# hermesONE_v2_0.net
KiCad netlist of a schematic drawn in EAGLE
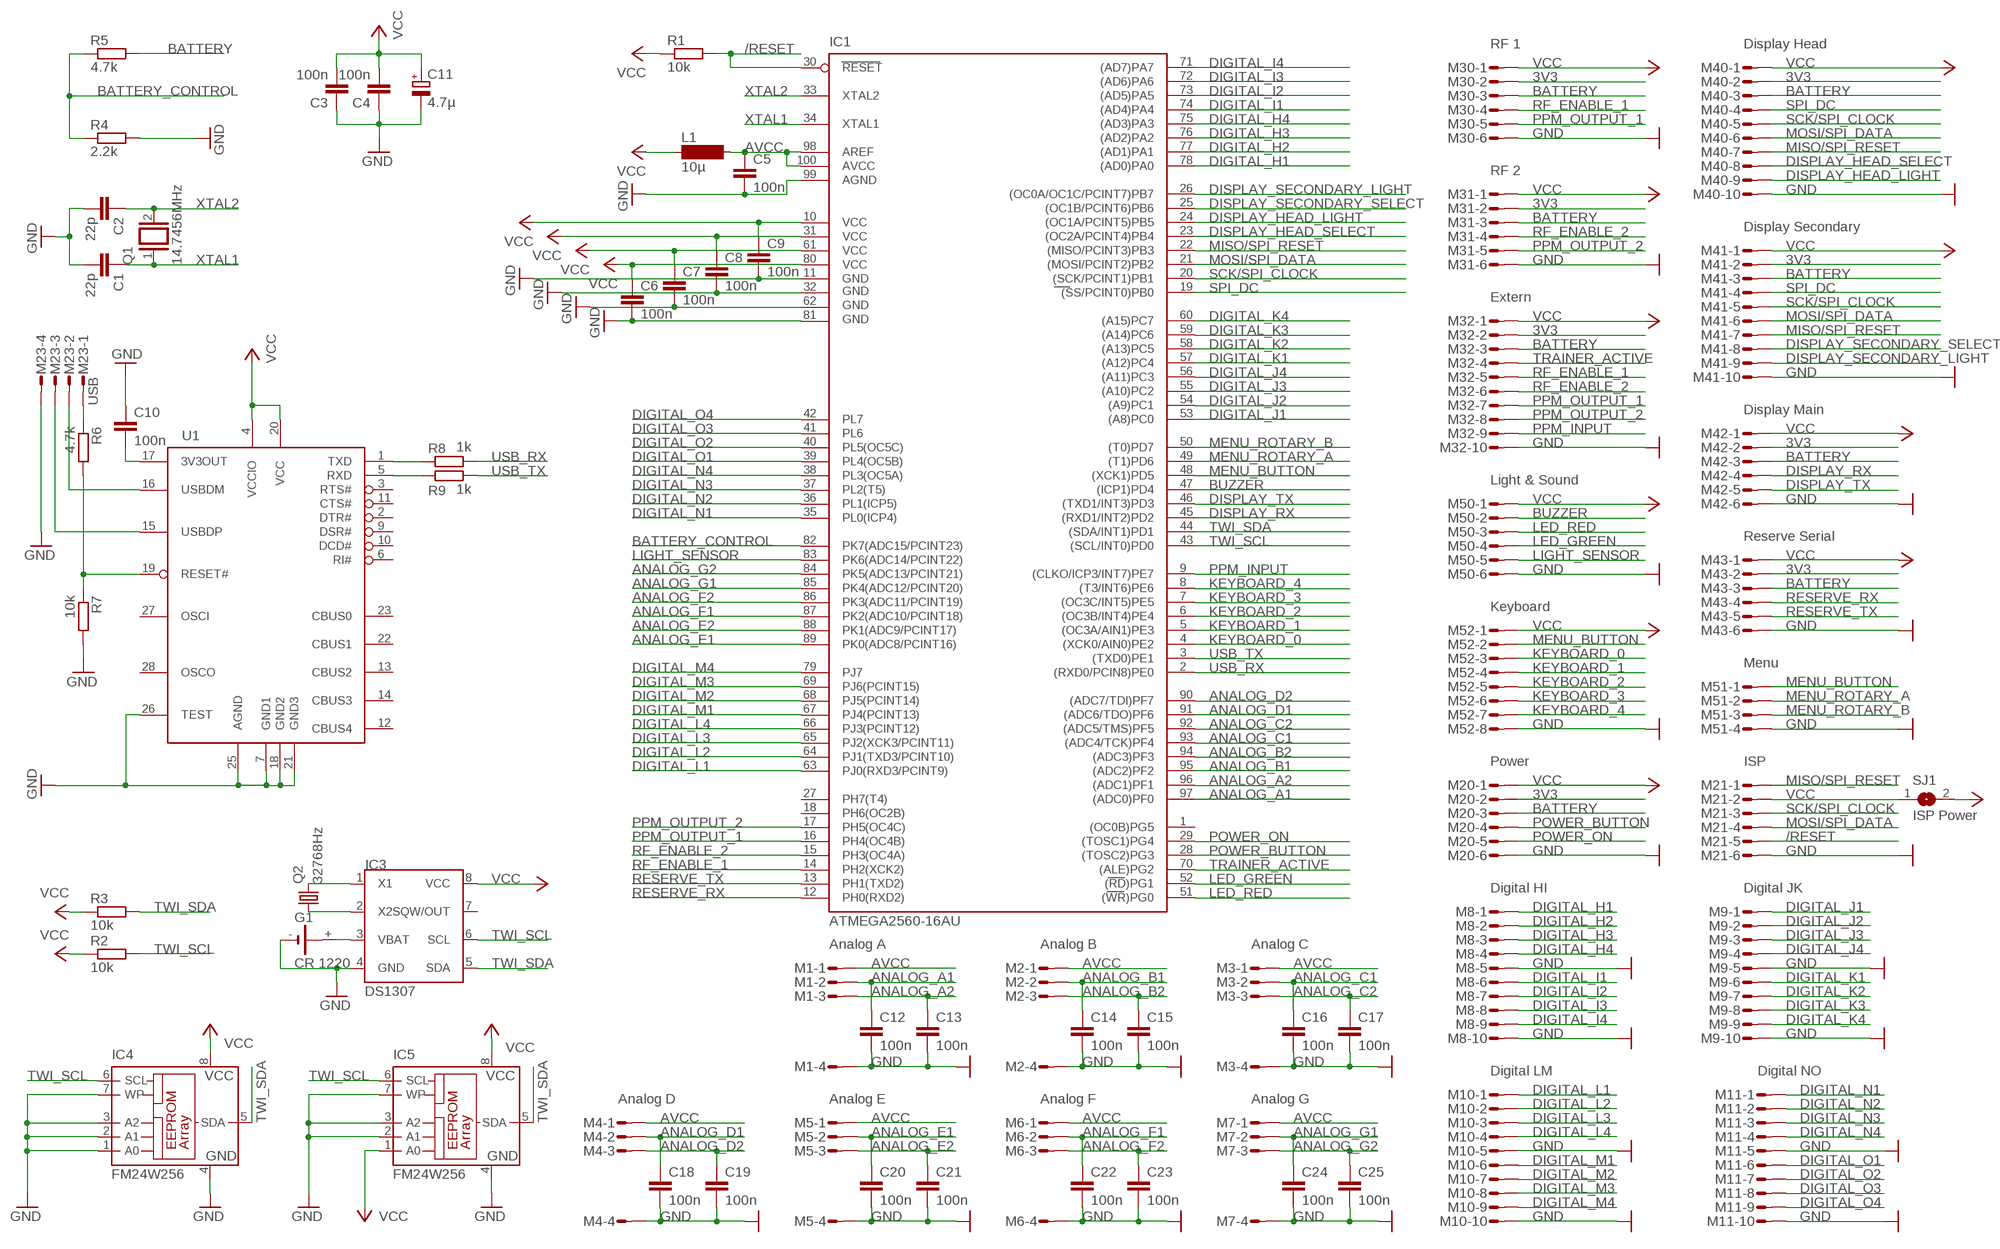
[diagram p0: schematic, sheet 1]

(export (version "E")
  (design (tool "Eeschema 10.0.6"))
  (components
    (comp (ref "C1")
      (value "22p")
      (footprint "eagle-import:C0603")
      (libsource (lib "eagle-import") (part "C-EUC0603"))
    )
    (comp (ref "C2")
      (value "22p")
      (footprint "eagle-import:C0603")
      (libsource (lib "eagle-import") (part "C-EUC0603"))
    )
    (comp (ref "C3")
      (value "100n")
      (footprint "eagle-import:C0603")
      (libsource (lib "eagle-import") (part "C-EUC0603"))
    )
    (comp (ref "C4")
      (value "100n")
      (footprint "eagle-import:C0603")
      (libsource (lib "eagle-import") (part "C-EUC0603"))
    )
    (comp (ref "C5")
      (value "100n")
      (footprint "eagle-import:C0603")
      (libsource (lib "eagle-import") (part "C-EUC0603"))
    )
    (comp (ref "C6")
      (value "100n")
      (footprint "eagle-import:C0603")
      (libsource (lib "eagle-import") (part "C-EUC0603"))
    )
    (comp (ref "C7")
      (value "100n")
      (footprint "eagle-import:C0603")
      (libsource (lib "eagle-import") (part "C-EUC0603"))
    )
    (comp (ref "C8")
      (value "100n")
      (footprint "eagle-import:C0603")
      (libsource (lib "eagle-import") (part "C-EUC0603"))
    )
    (comp (ref "C9")
      (value "100n")
      (footprint "eagle-import:C0603")
      (libsource (lib "eagle-import") (part "C-EUC0603"))
    )
    (comp (ref "C10")
      (value "100n")
      (footprint "eagle-import:C0603")
      (libsource (lib "eagle-import") (part "C-EUC0603"))
    )
    (comp (ref "C11")
      (value "4.7µ")
      (footprint "eagle-import:PANASONIC_B")
      (libsource (lib "eagle-import") (part "CPOL-EUB"))
    )
    (comp (ref "C12")
      (value "100n")
      (footprint "eagle-import:C0603")
      (libsource (lib "eagle-import") (part "C-EUC0603"))
    )
    (comp (ref "C13")
      (value "100n")
      (footprint "eagle-import:C0603")
      (libsource (lib "eagle-import") (part "C-EUC0603"))
    )
    (comp (ref "C14")
      (value "100n")
      (footprint "eagle-import:C0603")
      (libsource (lib "eagle-import") (part "C-EUC0603"))
    )
    (comp (ref "C15")
      (value "100n")
      (footprint "eagle-import:C0603")
      (libsource (lib "eagle-import") (part "C-EUC0603"))
    )
    (comp (ref "C16")
      (value "100n")
      (footprint "eagle-import:C0603")
      (libsource (lib "eagle-import") (part "C-EUC0603"))
    )
    (comp (ref "C17")
      (value "100n")
      (footprint "eagle-import:C0603")
      (libsource (lib "eagle-import") (part "C-EUC0603"))
    )
    (comp (ref "C18")
      (value "100n")
      (footprint "eagle-import:C0603")
      (libsource (lib "eagle-import") (part "C-EUC0603"))
    )
    (comp (ref "C19")
      (value "100n")
      (footprint "eagle-import:C0603")
      (libsource (lib "eagle-import") (part "C-EUC0603"))
    )
    (comp (ref "C20")
      (value "100n")
      (footprint "eagle-import:C0603")
      (libsource (lib "eagle-import") (part "C-EUC0603"))
    )
    (comp (ref "C21")
      (value "100n")
      (footprint "eagle-import:C0603")
      (libsource (lib "eagle-import") (part "C-EUC0603"))
    )
    (comp (ref "C22")
      (value "100n")
      (footprint "eagle-import:C0603")
      (libsource (lib "eagle-import") (part "C-EUC0603"))
    )
    (comp (ref "C23")
      (value "100n")
      (footprint "eagle-import:C0603")
      (libsource (lib "eagle-import") (part "C-EUC0603"))
    )
    (comp (ref "C24")
      (value "100n")
      (footprint "eagle-import:C0603")
      (libsource (lib "eagle-import") (part "C-EUC0603"))
    )
    (comp (ref "C25")
      (value "100n")
      (footprint "eagle-import:C0603")
      (libsource (lib "eagle-import") (part "C-EUC0603"))
    )
    (comp (ref "G1")
      (value "CR 1220")
      (footprint "eagle-import:KZH12THM")
      (libsource (lib "eagle-import") (part "1220"))
    )
    (comp (ref "IC1")
      (value "ATMEGA2560-16AU")
      (footprint "eagle-import:TQFP100")
      (libsource (lib "eagle-import") (part "ATMEGAAU2560-16"))
    )
    (comp (ref "IC3")
      (value "DS1307")
      (footprint "eagle-import:SOIC-8")
      (libsource (lib "eagle-import") (part "DS1307"))
    )
    (comp (ref "IC4")
      (value "FM24W256")
      (footprint "eagle-import:SO-08M")
      (fields (field (name "MF") "RAMTRON INTERNATIONAL CORP") (field (name "MPN") "FM24C64-S"))
      (libsource (lib "eagle-import") (part "24SMC64"))
    )
    (comp (ref "IC5")
      (value "FM24W256")
      (footprint "eagle-import:SO-08M")
      (fields (field (name "MF") "RAMTRON INTERNATIONAL CORP") (field (name "MPN") "FM24C64-S"))
      (libsource (lib "eagle-import") (part "24SMC64"))
    )
    (comp (ref "L1")
      (value "10µ")
      (footprint "eagle-import:SM-1206")
      (libsource (lib "eagle-import") (part "SM-1206"))
    )
    (comp (ref "M1")
      (value "Analog A")
      (footprint "eagle-import:MT-4")
      (fields (field (name "MPN") "7-215079-4"))
      (libsource (lib "eagle-import") (part "MT-4"))
    )
    (comp (ref "M2")
      (value "Analog B")
      (footprint "eagle-import:MT-4")
      (fields (field (name "MPN") "7-215079-4"))
      (libsource (lib "eagle-import") (part "MT-4"))
    )
    (comp (ref "M3")
      (value "Analog C")
      (footprint "eagle-import:MT-4")
      (fields (field (name "MPN") "7-215079-4"))
      (libsource (lib "eagle-import") (part "MT-4"))
    )
    (comp (ref "M4")
      (value "Analog D")
      (footprint "eagle-import:MT-4")
      (fields (field (name "MPN") "7-215079-4"))
      (libsource (lib "eagle-import") (part "MT-4"))
    )
    (comp (ref "M5")
      (value "Analog E")
      (footprint "eagle-import:MT-4")
      (fields (field (name "MPN") "7-215079-4"))
      (libsource (lib "eagle-import") (part "MT-4"))
    )
    (comp (ref "M6")
      (value "Analog F")
      (footprint "eagle-import:MT-4")
      (fields (field (name "MPN") "7-215079-4"))
      (libsource (lib "eagle-import") (part "MT-4"))
    )
    (comp (ref "M7")
      (value "Analog G")
      (footprint "eagle-import:MT-4")
      (fields (field (name "MPN") "7-215079-4"))
      (libsource (lib "eagle-import") (part "MT-4"))
    )
    (comp (ref "M8")
      (value "Digital HI")
      (footprint "eagle-import:MT-10")
      (fields (field (name "MF") "FARNELL") (field (name "MPN") "8-215079-0"))
      (libsource (lib "eagle-import") (part "MT-10"))
    )
    (comp (ref "M9")
      (value "Digital JK")
      (footprint "eagle-import:MT-10")
      (fields (field (name "MF") "FARNELL") (field (name "MPN") "8-215079-0"))
      (libsource (lib "eagle-import") (part "MT-10"))
    )
    (comp (ref "M10")
      (value "Digital LM")
      (footprint "eagle-import:MT-10")
      (fields (field (name "MF") "FARNELL") (field (name "MPN") "8-215079-0"))
      (libsource (lib "eagle-import") (part "MT-10"))
    )
    (comp (ref "M11")
      (value "Digital NO")
      (footprint "eagle-import:MT-10")
      (fields (field (name "MF") "FARNELL") (field (name "MPN") "8-215079-0"))
      (libsource (lib "eagle-import") (part "MT-10"))
    )
    (comp (ref "M20")
      (value "Power")
      (footprint "eagle-import:MT-6")
      (fields (field (name "MPN") "7-215079-6"))
      (libsource (lib "eagle-import") (part "MT-6"))
    )
    (comp (ref "M21")
      (value "ISP")
      (footprint "eagle-import:MT-6")
      (fields (field (name "MPN") "7-215079-6"))
      (libsource (lib "eagle-import") (part "MT-6"))
    )
    (comp (ref "M23")
      (value "USB")
      (footprint "eagle-import:MT-4")
      (fields (field (name "MPN") "7-215079-4"))
      (libsource (lib "eagle-import") (part "MT-4"))
    )
    (comp (ref "M30")
      (value "RF 1")
      (footprint "eagle-import:MT-6")
      (fields (field (name "MPN") "7-215079-6"))
      (libsource (lib "eagle-import") (part "MT-6"))
    )
    (comp (ref "M31")
      (value "RF 2")
      (footprint "eagle-import:MT-6")
      (fields (field (name "MPN") "7-215079-6"))
      (libsource (lib "eagle-import") (part "MT-6"))
    )
    (comp (ref "M32")
      (value "Extern")
      (footprint "eagle-import:MT-10")
      (fields (field (name "MF") "FARNELL") (field (name "MPN") "8-215079-0"))
      (libsource (lib "eagle-import") (part "MT-10"))
    )
    (comp (ref "M40")
      (value "Display Head")
      (footprint "eagle-import:MT-10")
      (fields (field (name "MF") "FARNELL") (field (name "MPN") "8-215079-0"))
      (libsource (lib "eagle-import") (part "MT-10"))
    )
    (comp (ref "M41")
      (value "Display Secondary")
      (footprint "eagle-import:MT-10")
      (fields (field (name "MF") "FARNELL") (field (name "MPN") "8-215079-0"))
      (libsource (lib "eagle-import") (part "MT-10"))
    )
    (comp (ref "M42")
      (value "Display Main")
      (footprint "eagle-import:MT-6")
      (fields (field (name "MPN") "7-215079-6"))
      (libsource (lib "eagle-import") (part "MT-6"))
    )
    (comp (ref "M43")
      (value "Reserve Serial")
      (footprint "eagle-import:MT-6")
      (fields (field (name "MPN") "7-215079-6"))
      (libsource (lib "eagle-import") (part "MT-6"))
    )
    (comp (ref "M50")
      (value "Light & Sound")
      (footprint "eagle-import:MT-6")
      (fields (field (name "MPN") "7-215079-6"))
      (libsource (lib "eagle-import") (part "MT-6"))
    )
    (comp (ref "M51")
      (value "Menu")
      (footprint "eagle-import:MT-4")
      (fields (field (name "MPN") "7-215079-4"))
      (libsource (lib "eagle-import") (part "MT-4"))
    )
    (comp (ref "M52")
      (value "Keyboard")
      (footprint "eagle-import:MT-8")
      (fields (field (name "MF") "FARNELL") (field (name "MPN") "7-215079-8"))
      (libsource (lib "eagle-import") (part "MT-8"))
    )
    (comp (ref "Q1")
      (value "14.7456MHz")
      (footprint "eagle-import:QS")
      (libsource (lib "eagle-import") (part "XTAL/S"))
    )
    (comp (ref "Q2")
      (value "32768Hz")
      (footprint "eagle-import:TC26H")
      (libsource (lib "eagle-import") (part "CRYSTALTC26H"))
    )
    (comp (ref "R1")
      (value "10k")
      (footprint "eagle-import:R0603")
      (libsource (lib "eagle-import") (part "R-EU_R0603"))
    )
    (comp (ref "R2")
      (value "10k")
      (footprint "eagle-import:R0603")
      (libsource (lib "eagle-import") (part "R-EU_R0603"))
    )
    (comp (ref "R3")
      (value "10k")
      (footprint "eagle-import:R0603")
      (libsource (lib "eagle-import") (part "R-EU_R0603"))
    )
    (comp (ref "R4")
      (value "2.2k")
      (footprint "eagle-import:R0603")
      (libsource (lib "eagle-import") (part "R-EU_R0603"))
    )
    (comp (ref "R5")
      (value "4.7k")
      (footprint "eagle-import:R0603")
      (libsource (lib "eagle-import") (part "R-EU_R0603"))
    )
    (comp (ref "R6")
      (value "4.7k")
      (footprint "eagle-import:R0603")
      (libsource (lib "eagle-import") (part "R-EU_R0603"))
    )
    (comp (ref "R7")
      (value "10k")
      (footprint "eagle-import:R0603")
      (libsource (lib "eagle-import") (part "R-EU_R0603"))
    )
    (comp (ref "R8")
      (value "1k")
      (footprint "eagle-import:R0603")
      (libsource (lib "eagle-import") (part "R-EU_R0603"))
    )
    (comp (ref "R9")
      (value "1k")
      (footprint "eagle-import:R0603")
      (libsource (lib "eagle-import") (part "R-EU_R0603"))
    )
    (comp (ref "SJ1")
      (value "ISP Power")
      (footprint "eagle-import:SJ")
      (libsource (lib "eagle-import") (part "SJ"))
    )
    (comp (ref "U1")
      (value "FT232R")
      (footprint "eagle-import:SSOP28DB")
      (libsource (lib "eagle-import") (part "FT232RL"))
    )
  )
  (nets
    (net (code "1") (name "/3V3") (class "Default")
      (node (ref "M20") (pin "2") (pinfunction "S_2") (pintype "passive"))
      (node (ref "M30") (pin "2") (pinfunction "S_2") (pintype "passive"))
      (node (ref "M31") (pin "2") (pinfunction "S_2") (pintype "passive"))
      (node (ref "M32") (pin "2") (pinfunction "S_2") (pintype "passive"))
      (node (ref "M40") (pin "2") (pinfunction "S_2") (pintype "passive"))
      (node (ref "M41") (pin "2") (pinfunction "S_2") (pintype "passive"))
      (node (ref "M42") (pin "2") (pinfunction "S_2") (pintype "passive"))
      (node (ref "M43") (pin "2") (pinfunction "S_2") (pintype "passive"))
    )
    (net (code "2") (name "/ANALOG_A1") (class "Default")
      (node (ref "C12") (pin "1") (pinfunction "1_1") (pintype "passive"))
      (node (ref "IC1") (pin "97") (pinfunction "(ADC0)PF0_97") (pintype "bidirectional"))
      (node (ref "M1") (pin "2") (pinfunction "S_2") (pintype "passive"))
    )
    (net (code "3") (name "/ANALOG_A2") (class "Default")
      (node (ref "C13") (pin "1") (pinfunction "1_1") (pintype "passive"))
      (node (ref "IC1") (pin "96") (pinfunction "(ADC1)PF1_96") (pintype "bidirectional"))
      (node (ref "M1") (pin "3") (pinfunction "S_3") (pintype "passive"))
    )
    (net (code "4") (name "/ANALOG_B1") (class "Default")
      (node (ref "C14") (pin "1") (pinfunction "1_1") (pintype "passive"))
      (node (ref "IC1") (pin "95") (pinfunction "(ADC2)PF2_95") (pintype "bidirectional"))
      (node (ref "M2") (pin "2") (pinfunction "S_2") (pintype "passive"))
    )
    (net (code "5") (name "/ANALOG_B2") (class "Default")
      (node (ref "C15") (pin "1") (pinfunction "1_1") (pintype "passive"))
      (node (ref "IC1") (pin "94") (pinfunction "(ADC3)PF3_94") (pintype "bidirectional"))
      (node (ref "M2") (pin "3") (pinfunction "S_3") (pintype "passive"))
    )
    (net (code "6") (name "/ANALOG_C1") (class "Default")
      (node (ref "C16") (pin "1") (pinfunction "1_1") (pintype "passive"))
      (node (ref "IC1") (pin "93") (pinfunction "(ADC4/TCK)PF4_93") (pintype "bidirectional"))
      (node (ref "M3") (pin "2") (pinfunction "S_2") (pintype "passive"))
    )
    (net (code "7") (name "/ANALOG_C2") (class "Default")
      (node (ref "C17") (pin "1") (pinfunction "1_1") (pintype "passive"))
      (node (ref "IC1") (pin "92") (pinfunction "(ADC5/TMS)PF5_92") (pintype "bidirectional"))
      (node (ref "M3") (pin "3") (pinfunction "S_3") (pintype "passive"))
    )
    (net (code "8") (name "/ANALOG_D1") (class "Default")
      (node (ref "C18") (pin "1") (pinfunction "1_1") (pintype "passive"))
      (node (ref "IC1") (pin "91") (pinfunction "(ADC6/TDO)PF6_91") (pintype "bidirectional"))
      (node (ref "M4") (pin "2") (pinfunction "S_2") (pintype "passive"))
    )
    (net (code "9") (name "/ANALOG_D2") (class "Default")
      (node (ref "C19") (pin "1") (pinfunction "1_1") (pintype "passive"))
      (node (ref "IC1") (pin "90") (pinfunction "(ADC7/TDI)PF7_90") (pintype "bidirectional"))
      (node (ref "M4") (pin "3") (pinfunction "S_3") (pintype "passive"))
    )
    (net (code "10") (name "/ANALOG_E1") (class "Default")
      (node (ref "C20") (pin "1") (pinfunction "1_1") (pintype "passive"))
      (node (ref "IC1") (pin "89") (pinfunction "PK0(ADC8/PCINT16)_89") (pintype "bidirectional"))
      (node (ref "M5") (pin "2") (pinfunction "S_2") (pintype "passive"))
    )
    (net (code "11") (name "/ANALOG_E2") (class "Default")
      (node (ref "C21") (pin "1") (pinfunction "1_1") (pintype "passive"))
      (node (ref "IC1") (pin "88") (pinfunction "PK1(ADC9/PCINT17)_88") (pintype "bidirectional"))
      (node (ref "M5") (pin "3") (pinfunction "S_3") (pintype "passive"))
    )
    (net (code "12") (name "/ANALOG_F1") (class "Default")
      (node (ref "C22") (pin "1") (pinfunction "1_1") (pintype "passive"))
      (node (ref "IC1") (pin "87") (pinfunction "PK2(ADC10/PCINT18)_87") (pintype "bidirectional"))
      (node (ref "M6") (pin "2") (pinfunction "S_2") (pintype "passive"))
    )
    (net (code "13") (name "/ANALOG_F2") (class "Default")
      (node (ref "C23") (pin "1") (pinfunction "1_1") (pintype "passive"))
      (node (ref "IC1") (pin "86") (pinfunction "PK3(ADC11/PCINT19)_86") (pintype "bidirectional"))
      (node (ref "M6") (pin "3") (pinfunction "S_3") (pintype "passive"))
    )
    (net (code "14") (name "/ANALOG_G1") (class "Default")
      (node (ref "C24") (pin "1") (pinfunction "1_1") (pintype "passive"))
      (node (ref "IC1") (pin "85") (pinfunction "PK4(ADC12/PCINT20)_85") (pintype "bidirectional"))
      (node (ref "M7") (pin "2") (pinfunction "S_2") (pintype "passive"))
    )
    (net (code "15") (name "/ANALOG_G2") (class "Default")
      (node (ref "C25") (pin "1") (pinfunction "1_1") (pintype "passive"))
      (node (ref "IC1") (pin "84") (pinfunction "PK5(ADC13/PCINT21)_84") (pintype "bidirectional"))
      (node (ref "M7") (pin "3") (pinfunction "S_3") (pintype "passive"))
    )
    (net (code "16") (name "/AVCC") (class "Default")
      (node (ref "C5") (pin "1") (pinfunction "1_1") (pintype "passive"))
      (node (ref "IC1") (pin "100") (pinfunction "AVCC_100") (pintype "power_in"))
      (node (ref "IC1") (pin "98") (pinfunction "AREF_98") (pintype "bidirectional"))
      (node (ref "L1") (pin "2") (pinfunction "2_2") (pintype "passive"))
      (node (ref "M1") (pin "1") (pinfunction "S_1") (pintype "passive"))
      (node (ref "M2") (pin "1") (pinfunction "S_1") (pintype "passive"))
      (node (ref "M3") (pin "1") (pinfunction "S_1") (pintype "passive"))
      (node (ref "M4") (pin "1") (pinfunction "S_1") (pintype "passive"))
      (node (ref "M5") (pin "1") (pinfunction "S_1") (pintype "passive"))
      (node (ref "M6") (pin "1") (pinfunction "S_1") (pintype "passive"))
      (node (ref "M7") (pin "1") (pinfunction "S_1") (pintype "passive"))
    )
    (net (code "17") (name "/BATTERY") (class "Default")
      (node (ref "M20") (pin "3") (pinfunction "S_3") (pintype "passive"))
      (node (ref "M30") (pin "3") (pinfunction "S_3") (pintype "passive"))
      (node (ref "M31") (pin "3") (pinfunction "S_3") (pintype "passive"))
      (node (ref "M32") (pin "3") (pinfunction "S_3") (pintype "passive"))
      (node (ref "M40") (pin "3") (pinfunction "S_3") (pintype "passive"))
      (node (ref "M41") (pin "3") (pinfunction "S_3") (pintype "passive"))
      (node (ref "M42") (pin "3") (pinfunction "S_3") (pintype "passive"))
      (node (ref "M43") (pin "3") (pinfunction "S_3") (pintype "passive"))
      (node (ref "R5") (pin "2") (pinfunction "2_2") (pintype "passive"))
    )
    (net (code "18") (name "/BATTERY_CONTROL") (class "Default")
      (node (ref "IC1") (pin "82") (pinfunction "PK7(ADC15/PCINT23)_82") (pintype "bidirectional"))
      (node (ref "R4") (pin "1") (pinfunction "1_1") (pintype "passive"))
      (node (ref "R5") (pin "1") (pinfunction "1_1") (pintype "passive"))
    )
    (net (code "19") (name "/BUZZER") (class "Default")
      (node (ref "IC1") (pin "47") (pinfunction "(ICP1)PD4_47") (pintype "bidirectional"))
      (node (ref "M50") (pin "2") (pinfunction "S_2") (pintype "passive"))
    )
    (net (code "20") (name "/DIGITAL_H1") (class "Default")
      (node (ref "IC1") (pin "78") (pinfunction "(AD0)PA0_78") (pintype "bidirectional"))
      (node (ref "M8") (pin "1") (pinfunction "S_1") (pintype "passive"))
    )
    (net (code "21") (name "/DIGITAL_H2") (class "Default")
      (node (ref "IC1") (pin "77") (pinfunction "(AD1)PA1_77") (pintype "bidirectional"))
      (node (ref "M8") (pin "2") (pinfunction "S_2") (pintype "passive"))
    )
    (net (code "22") (name "/DIGITAL_H3") (class "Default")
      (node (ref "IC1") (pin "76") (pinfunction "(AD2)PA2_76") (pintype "bidirectional"))
      (node (ref "M8") (pin "3") (pinfunction "S_3") (pintype "passive"))
    )
    (net (code "23") (name "/DIGITAL_H4") (class "Default")
      (node (ref "IC1") (pin "75") (pinfunction "(AD3)PA3_75") (pintype "bidirectional"))
      (node (ref "M8") (pin "4") (pinfunction "S_4") (pintype "passive"))
    )
    (net (code "24") (name "/DIGITAL_I1") (class "Default")
      (node (ref "IC1") (pin "74") (pinfunction "(AD4)PA4_74") (pintype "bidirectional"))
      (node (ref "M8") (pin "6") (pinfunction "S_6") (pintype "passive"))
    )
    (net (code "25") (name "/DIGITAL_I2") (class "Default")
      (node (ref "IC1") (pin "73") (pinfunction "(AD5)PA5_73") (pintype "bidirectional"))
      (node (ref "M8") (pin "7") (pinfunction "S_7") (pintype "passive"))
    )
    (net (code "26") (name "/DIGITAL_I3") (class "Default")
      (node (ref "IC1") (pin "72") (pinfunction "(AD6)PA6_72") (pintype "bidirectional"))
      (node (ref "M8") (pin "8") (pinfunction "S_8") (pintype "passive"))
    )
    (net (code "27") (name "/DIGITAL_I4") (class "Default")
      (node (ref "IC1") (pin "71") (pinfunction "(AD7)PA7_71") (pintype "bidirectional"))
      (node (ref "M8") (pin "9") (pinfunction "S_9") (pintype "passive"))
    )
    (net (code "28") (name "/DIGITAL_J1") (class "Default")
      (node (ref "IC1") (pin "53") (pinfunction "(A8)PC0_53") (pintype "bidirectional"))
      (node (ref "M9") (pin "1") (pinfunction "S_1") (pintype "passive"))
    )
    (net (code "29") (name "/DIGITAL_J2") (class "Default")
      (node (ref "IC1") (pin "54") (pinfunction "(A9)PC1_54") (pintype "bidirectional"))
      (node (ref "M9") (pin "2") (pinfunction "S_2") (pintype "passive"))
    )
    (net (code "30") (name "/DIGITAL_J3") (class "Default")
      (node (ref "IC1") (pin "55") (pinfunction "(A10)PC2_55") (pintype "bidirectional"))
      (node (ref "M9") (pin "3") (pinfunction "S_3") (pintype "passive"))
    )
    (net (code "31") (name "/DIGITAL_J4") (class "Default")
      (node (ref "IC1") (pin "56") (pinfunction "(A11)PC3_56") (pintype "bidirectional"))
      (node (ref "M9") (pin "4") (pinfunction "S_4") (pintype "passive"))
    )
    (net (code "32") (name "/DIGITAL_K1") (class "Default")
      (node (ref "IC1") (pin "57") (pinfunction "(A12)PC4_57") (pintype "bidirectional"))
      (node (ref "M9") (pin "6") (pinfunction "S_6") (pintype "passive"))
    )
    (net (code "33") (name "/DIGITAL_K2") (class "Default")
      (node (ref "IC1") (pin "58") (pinfunction "(A13)PC5_58") (pintype "bidirectional"))
      (node (ref "M9") (pin "7") (pinfunction "S_7") (pintype "passive"))
    )
    (net (code "34") (name "/DIGITAL_K3") (class "Default")
      (node (ref "IC1") (pin "59") (pinfunction "(A14)PC6_59") (pintype "bidirectional"))
      (node (ref "M9") (pin "8") (pinfunction "S_8") (pintype "passive"))
    )
    (net (code "35") (name "/DIGITAL_K4") (class "Default")
      (node (ref "IC1") (pin "60") (pinfunction "(A15)PC7_60") (pintype "bidirectional"))
      (node (ref "M9") (pin "9") (pinfunction "S_9") (pintype "passive"))
    )
    (net (code "36") (name "/DIGITAL_L1") (class "Default")
      (node (ref "IC1") (pin "63") (pinfunction "PJ0(RXD3/PCINT9)_63") (pintype "bidirectional"))
      (node (ref "M10") (pin "1") (pinfunction "S_1") (pintype "passive"))
    )
    (net (code "37") (name "/DIGITAL_L2") (class "Default")
      (node (ref "IC1") (pin "64") (pinfunction "PJ1(TXD3/PCINT10)_64") (pintype "bidirectional"))
      (node (ref "M10") (pin "2") (pinfunction "S_2") (pintype "passive"))
    )
    (net (code "38") (name "/DIGITAL_L3") (class "Default")
      (node (ref "IC1") (pin "65") (pinfunction "PJ2(XCK3/PCINT11)_65") (pintype "bidirectional"))
      (node (ref "M10") (pin "3") (pinfunction "S_3") (pintype "passive"))
    )
    (net (code "39") (name "/DIGITAL_L4") (class "Default")
      (node (ref "IC1") (pin "66") (pinfunction "PJ3(PCINT12)_66") (pintype "bidirectional"))
      (node (ref "M10") (pin "4") (pinfunction "S_4") (pintype "passive"))
    )
    (net (code "40") (name "/DIGITAL_M1") (class "Default")
      (node (ref "IC1") (pin "67") (pinfunction "PJ4(PCINT13)_67") (pintype "bidirectional"))
      (node (ref "M10") (pin "6") (pinfunction "S_6") (pintype "passive"))
    )
    (net (code "41") (name "/DIGITAL_M2") (class "Default")
      (node (ref "IC1") (pin "68") (pinfunction "PJ5(PCINT14)_68") (pintype "bidirectional"))
      (node (ref "M10") (pin "7") (pinfunction "S_7") (pintype "passive"))
    )
    (net (code "42") (name "/DIGITAL_M3") (class "Default")
      (node (ref "IC1") (pin "69") (pinfunction "PJ6(PCINT15)_69") (pintype "bidirectional"))
      (node (ref "M10") (pin "8") (pinfunction "S_8") (pintype "passive"))
    )
    (net (code "43") (name "/DIGITAL_M4") (class "Default")
      (node (ref "IC1") (pin "79") (pinfunction "PJ7_79") (pintype "bidirectional"))
      (node (ref "M10") (pin "9") (pinfunction "S_9") (pintype "passive"))
    )
    (net (code "44") (name "/DIGITAL_N1") (class "Default")
      (node (ref "IC1") (pin "35") (pinfunction "PL0(ICP4)_35") (pintype "bidirectional"))
      (node (ref "M11") (pin "1") (pinfunction "S_1") (pintype "passive"))
    )
    (net (code "45") (name "/DIGITAL_N2") (class "Default")
      (node (ref "IC1") (pin "36") (pinfunction "PL1(ICP5)_36") (pintype "bidirectional"))
      (node (ref "M11") (pin "2") (pinfunction "S_2") (pintype "passive"))
    )
    (net (code "46") (name "/DIGITAL_N3") (class "Default")
      (node (ref "IC1") (pin "37") (pinfunction "PL2(T5)_37") (pintype "bidirectional"))
      (node (ref "M11") (pin "3") (pinfunction "S_3") (pintype "passive"))
    )
    (net (code "47") (name "/DIGITAL_N4") (class "Default")
      (node (ref "IC1") (pin "38") (pinfunction "PL3(OC5A)_38") (pintype "bidirectional"))
      (node (ref "M11") (pin "4") (pinfunction "S_4") (pintype "passive"))
    )
    (net (code "48") (name "/DIGITAL_O1") (class "Default")
      (node (ref "IC1") (pin "39") (pinfunction "PL4(OC5B)_39") (pintype "bidirectional"))
      (node (ref "M11") (pin "6") (pinfunction "S_6") (pintype "passive"))
    )
    (net (code "49") (name "/DIGITAL_O2") (class "Default")
      (node (ref "IC1") (pin "40") (pinfunction "PL5(OC5C)_40") (pintype "bidirectional"))
      (node (ref "M11") (pin "7") (pinfunction "S_7") (pintype "passive"))
    )
    (net (code "50") (name "/DIGITAL_O3") (class "Default")
      (node (ref "IC1") (pin "41") (pinfunction "PL6_41") (pintype "bidirectional"))
      (node (ref "M11") (pin "8") (pinfunction "S_8") (pintype "passive"))
    )
    (net (code "51") (name "/DIGITAL_O4") (class "Default")
      (node (ref "IC1") (pin "42") (pinfunction "PL7_42") (pintype "bidirectional"))
      (node (ref "M11") (pin "9") (pinfunction "S_9") (pintype "passive"))
    )
    (net (code "52") (name "/DISPLAY_HEAD_LIGHT") (class "Default")
      (node (ref "IC1") (pin "24") (pinfunction "(OC1A/PCINT5)PB5_24") (pintype "bidirectional"))
      (node (ref "M40") (pin "9") (pinfunction "S_9") (pintype "passive"))
    )
    (net (code "53") (name "/DISPLAY_HEAD_SELECT") (class "Default")
      (node (ref "IC1") (pin "23") (pinfunction "(OC2A/PCINT4)PB4_23") (pintype "bidirectional"))
      (node (ref "M40") (pin "8") (pinfunction "S_8") (pintype "passive"))
    )
    (net (code "54") (name "/DISPLAY_RX") (class "Default")
      (node (ref "IC1") (pin "45") (pinfunction "(RXD1/INT2)PD2_45") (pintype "bidirectional"))
      (node (ref "M42") (pin "4") (pinfunction "S_4") (pintype "passive"))
    )
    (net (code "55") (name "/DISPLAY_SECONDARY_LIGHT") (class "Default")
      (node (ref "IC1") (pin "26") (pinfunction "(OC0A/OC1C/PCINT7)PB7_26") (pintype "bidirectional"))
      (node (ref "M41") (pin "9") (pinfunction "S_9") (pintype "passive"))
    )
    (net (code "56") (name "/DISPLAY_SECONDARY_SELECT") (class "Default")
      (node (ref "IC1") (pin "25") (pinfunction "(OC1B/PCINT6)PB6_25") (pintype "bidirectional"))
      (node (ref "M41") (pin "8") (pinfunction "S_8") (pintype "passive"))
    )
    (net (code "57") (name "/DISPLAY_TX") (class "Default")
      (node (ref "IC1") (pin "46") (pinfunction "(TXD1/INT3)PD3_46") (pintype "bidirectional"))
      (node (ref "M42") (pin "5") (pinfunction "S_5") (pintype "passive"))
    )
    (net (code "58") (name "/KEYBOARD_0") (class "Default")
      (node (ref "IC1") (pin "4") (pinfunction "(XCK0/AIN0)PE2_4") (pintype "bidirectional"))
      (node (ref "M52") (pin "3") (pinfunction "S_3") (pintype "passive"))
    )
    (net (code "59") (name "/KEYBOARD_1") (class "Default")
      (node (ref "IC1") (pin "5") (pinfunction "(OC3A/AIN1)PE3_5") (pintype "bidirectional"))
      (node (ref "M52") (pin "4") (pinfunction "S_4") (pintype "passive"))
    )
    (net (code "60") (name "/KEYBOARD_2") (class "Default")
      (node (ref "IC1") (pin "6") (pinfunction "(OC3B/INT4)PE4_6") (pintype "bidirectional"))
      (node (ref "M52") (pin "5") (pinfunction "S_5") (pintype "passive"))
    )
    (net (code "61") (name "/KEYBOARD_3") (class "Default")
      (node (ref "IC1") (pin "7") (pinfunction "(OC3C/INT5)PE5_7") (pintype "bidirectional"))
      (node (ref "M52") (pin "6") (pinfunction "S_6") (pintype "passive"))
    )
    (net (code "62") (name "/KEYBOARD_4") (class "Default")
      (node (ref "IC1") (pin "8") (pinfunction "(T3/INT6)PE6_8") (pintype "bidirectional"))
      (node (ref "M52") (pin "7") (pinfunction "S_7") (pintype "passive"))
    )
    (net (code "63") (name "/LED_GREEN") (class "Default")
      (node (ref "IC1") (pin "52") (pinfunction "(RD)PG1_52") (pintype "bidirectional"))
      (node (ref "M50") (pin "4") (pinfunction "S_4") (pintype "passive"))
    )
    (net (code "64") (name "/LED_RED") (class "Default")
      (node (ref "IC1") (pin "51") (pinfunction "(WR)PG0_51") (pintype "bidirectional"))
      (node (ref "M50") (pin "3") (pinfunction "S_3") (pintype "passive"))
    )
    (net (code "65") (name "/LIGHT_SENSOR") (class "Default")
      (node (ref "IC1") (pin "83") (pinfunction "PK6(ADC14/PCINT22)_83") (pintype "bidirectional"))
      (node (ref "M50") (pin "5") (pinfunction "S_5") (pintype "passive"))
    )
    (net (code "66") (name "/MENU_BUTTON") (class "Default")
      (node (ref "IC1") (pin "48") (pinfunction "(XCK1)PD5_48") (pintype "bidirectional"))
      (node (ref "M51") (pin "1") (pinfunction "S_1") (pintype "passive"))
      (node (ref "M52") (pin "2") (pinfunction "S_2") (pintype "passive"))
    )
    (net (code "67") (name "/MENU_ROTARY_A") (class "Default")
      (node (ref "IC1") (pin "49") (pinfunction "(T1)PD6_49") (pintype "bidirectional"))
      (node (ref "M51") (pin "2") (pinfunction "S_2") (pintype "passive"))
    )
    (net (code "68") (name "/MENU_ROTARY_B") (class "Default")
      (node (ref "IC1") (pin "50") (pinfunction "(T0)PD7_50") (pintype "bidirectional"))
      (node (ref "M51") (pin "3") (pinfunction "S_3") (pintype "passive"))
    )
    (net (code "69") (name "/MISO{slash}SPI_RESET") (class "Default")
      (node (ref "IC1") (pin "22") (pinfunction "(MISO/PCINT3)PB3_22") (pintype "bidirectional"))
      (node (ref "M21") (pin "1") (pinfunction "S_1") (pintype "passive"))
      (node (ref "M40") (pin "7") (pinfunction "S_7") (pintype "passive"))
      (node (ref "M41") (pin "7") (pinfunction "S_7") (pintype "passive"))
    )
    (net (code "70") (name "/MOSI{slash}SPI_DATA") (class "Default")
      (node (ref "IC1") (pin "21") (pinfunction "(MOSI/PCINT2)PB2_21") (pintype "bidirectional"))
      (node (ref "M21") (pin "4") (pinfunction "S_4") (pintype "passive"))
      (node (ref "M40") (pin "6") (pinfunction "S_6") (pintype "passive"))
      (node (ref "M41") (pin "6") (pinfunction "S_6") (pintype "passive"))
    )
    (net (code "71") (name "/POWER_BUTTON") (class "Default")
      (node (ref "IC1") (pin "28") (pinfunction "(TOSC2)PG3_28") (pintype "bidirectional"))
      (node (ref "M20") (pin "4") (pinfunction "S_4") (pintype "passive"))
    )
    (net (code "72") (name "/POWER_ON") (class "Default")
      (node (ref "IC1") (pin "29") (pinfunction "(TOSC1)PG4_29") (pintype "bidirectional"))
      (node (ref "M20") (pin "5") (pinfunction "S_5") (pintype "passive"))
    )
    (net (code "73") (name "/PPM_INPUT") (class "Default")
      (node (ref "IC1") (pin "9") (pinfunction "(CLKO/ICP3/INT7)PE7_9") (pintype "bidirectional"))
      (node (ref "M32") (pin "9") (pinfunction "S_9") (pintype "passive"))
    )
    (net (code "74") (name "/PPM_OUTPUT_1") (class "Default")
      (node (ref "IC1") (pin "16") (pinfunction "PH4(OC4B)_16") (pintype "bidirectional"))
      (node (ref "M30") (pin "5") (pinfunction "S_5") (pintype "passive"))
      (node (ref "M32") (pin "7") (pinfunction "S_7") (pintype "passive"))
    )
    (net (code "75") (name "/PPM_OUTPUT_2") (class "Default")
      (node (ref "IC1") (pin "17") (pinfunction "PH5(OC4C)_17") (pintype "bidirectional"))
      (node (ref "M31") (pin "5") (pinfunction "S_5") (pintype "passive"))
      (node (ref "M32") (pin "8") (pinfunction "S_8") (pintype "passive"))
    )
    (net (code "76") (name "/RESERVE_RX") (class "Default")
      (node (ref "IC1") (pin "12") (pinfunction "PH0(RXD2)_12") (pintype "bidirectional"))
      (node (ref "M43") (pin "4") (pinfunction "S_4") (pintype "passive"))
    )
    (net (code "77") (name "/RESERVE_TX") (class "Default")
      (node (ref "IC1") (pin "13") (pinfunction "PH1(TXD2)_13") (pintype "bidirectional"))
      (node (ref "M43") (pin "5") (pinfunction "S_5") (pintype "passive"))
    )
    (net (code "78") (name "/RF_ENABLE_1") (class "Default")
      (node (ref "IC1") (pin "14") (pinfunction "PH2(XCK2)_14") (pintype "bidirectional"))
      (node (ref "M30") (pin "4") (pinfunction "S_4") (pintype "passive"))
      (node (ref "M32") (pin "5") (pinfunction "S_5") (pintype "passive"))
    )
    (net (code "79") (name "/RF_ENABLE_2") (class "Default")
      (node (ref "IC1") (pin "15") (pinfunction "PH3(OC4A)_15") (pintype "bidirectional"))
      (node (ref "M31") (pin "4") (pinfunction "S_4") (pintype "passive"))
      (node (ref "M32") (pin "6") (pinfunction "S_6") (pintype "passive"))
    )
    (net (code "80") (name "/SCK{slash}SPI_CLOCK") (class "Default")
      (node (ref "IC1") (pin "20") (pinfunction "(SCK/PCINT1)PB1_20") (pintype "bidirectional"))
      (node (ref "M21") (pin "3") (pinfunction "S_3") (pintype "passive"))
      (node (ref "M40") (pin "5") (pinfunction "S_5") (pintype "passive"))
      (node (ref "M41") (pin "5") (pinfunction "S_5") (pintype "passive"))
    )
    (net (code "81") (name "/SPI_DC") (class "Default")
      (node (ref "IC1") (pin "19") (pinfunction "(SS/PCINT0)PB0_19") (pintype "bidirectional"))
      (node (ref "M40") (pin "4") (pinfunction "S_4") (pintype "passive"))
      (node (ref "M41") (pin "4") (pinfunction "S_4") (pintype "passive"))
    )
    (net (code "82") (name "/TRAINER_ACTIVE") (class "Default")
      (node (ref "IC1") (pin "70") (pinfunction "(ALE)PG2_70") (pintype "bidirectional"))
      (node (ref "M32") (pin "4") (pinfunction "S_4") (pintype "passive"))
    )
    (net (code "83") (name "/TWI_SCL") (class "Default")
      (node (ref "IC1") (pin "43") (pinfunction "(SCL/INT0)PD0_43") (pintype "bidirectional"))
      (node (ref "IC3") (pin "6") (pinfunction "SCL_6") (pintype "input"))
      (node (ref "IC4") (pin "6") (pinfunction "SCL_6") (pintype "input"))
      (node (ref "IC5") (pin "6") (pinfunction "SCL_6") (pintype "input"))
      (node (ref "R2") (pin "2") (pinfunction "2_2") (pintype "passive"))
    )
    (net (code "84") (name "/TWI_SDA") (class "Default")
      (node (ref "IC1") (pin "44") (pinfunction "(SDA/INT1)PD1_44") (pintype "bidirectional"))
      (node (ref "IC3") (pin "5") (pinfunction "SDA_5") (pintype "bidirectional"))
      (node (ref "IC4") (pin "5") (pinfunction "SDA_5") (pintype "bidirectional"))
      (node (ref "IC5") (pin "5") (pinfunction "SDA_5") (pintype "bidirectional"))
      (node (ref "R3") (pin "2") (pinfunction "2_2") (pintype "passive"))
    )
    (net (code "85") (name "/USB_RX") (class "Default")
      (node (ref "IC1") (pin "2") (pinfunction "(RXD0/PCIN8)PE0_2") (pintype "bidirectional"))
      (node (ref "R8") (pin "2") (pinfunction "2_2") (pintype "passive"))
    )
    (net (code "86") (name "/USB_TX") (class "Default")
      (node (ref "IC1") (pin "3") (pinfunction "(TXD0)PE1_3") (pintype "bidirectional"))
      (node (ref "R9") (pin "2") (pinfunction "2_2") (pintype "passive"))
    )
    (net (code "87") (name "/XTAL1") (class "Default")
      (node (ref "C1") (pin "1") (pinfunction "1_1") (pintype "passive"))
      (node (ref "IC1") (pin "34") (pinfunction "XTAL1_34") (pintype "input"))
      (node (ref "Q1") (pin "1") (pinfunction "1_1") (pintype "passive"))
    )
    (net (code "88") (name "/XTAL2") (class "Default")
      (node (ref "C2") (pin "1") (pinfunction "1_1") (pintype "passive"))
      (node (ref "IC1") (pin "33") (pinfunction "XTAL2_33") (pintype "output"))
      (node (ref "Q1") (pin "2") (pinfunction "2_2") (pintype "passive"))
    )
    (net (code "89") (name "/{slash}RESET") (class "Default")
      (node (ref "IC1") (pin "30") (pinfunction "RESET_30") (pintype "input"))
      (node (ref "M21") (pin "5") (pinfunction "S_5") (pintype "passive"))
      (node (ref "R1") (pin "2") (pinfunction "2_2") (pintype "passive"))
    )
    (net (code "90") (name "GND") (class "Default")
      (node (ref "C1") (pin "2") (pinfunction "2_2") (pintype "passive"))
      (node (ref "C10") (pin "1") (pinfunction "1_1") (pintype "passive"))
      (node (ref "C11") (pin "-") (pinfunction "-_-") (pintype "passive"))
      (node (ref "C12") (pin "2") (pinfunction "2_2") (pintype "passive"))
      (node (ref "C13") (pin "2") (pinfunction "2_2") (pintype "passive"))
      (node (ref "C14") (pin "2") (pinfunction "2_2") (pintype "passive"))
      (node (ref "C15") (pin "2") (pinfunction "2_2") (pintype "passive"))
      (node (ref "C16") (pin "2") (pinfunction "2_2") (pintype "passive"))
      (node (ref "C17") (pin "2") (pinfunction "2_2") (pintype "passive"))
      (node (ref "C18") (pin "2") (pinfunction "2_2") (pintype "passive"))
      (node (ref "C19") (pin "2") (pinfunction "2_2") (pintype "passive"))
      (node (ref "C2") (pin "2") (pinfunction "2_2") (pintype "passive"))
      (node (ref "C20") (pin "2") (pinfunction "2_2") (pintype "passive"))
      (node (ref "C21") (pin "2") (pinfunction "2_2") (pintype "passive"))
      (node (ref "C22") (pin "2") (pinfunction "2_2") (pintype "passive"))
      (node (ref "C23") (pin "2") (pinfunction "2_2") (pintype "passive"))
      (node (ref "C24") (pin "2") (pinfunction "2_2") (pintype "passive"))
      (node (ref "C25") (pin "2") (pinfunction "2_2") (pintype "passive"))
      (node (ref "C3") (pin "1") (pinfunction "1_1") (pintype "passive"))
      (node (ref "C4") (pin "1") (pinfunction "1_1") (pintype "passive"))
      (node (ref "C5") (pin "2") (pinfunction "2_2") (pintype "passive"))
      (node (ref "C6") (pin "2") (pinfunction "2_2") (pintype "passive"))
      (node (ref "C7") (pin "2") (pinfunction "2_2") (pintype "passive"))
      (node (ref "C8") (pin "2") (pinfunction "2_2") (pintype "passive"))
      (node (ref "C9") (pin "2") (pinfunction "2_2") (pintype "passive"))
      (node (ref "G1") (pin "-") (pinfunction "-_-") (pintype "passive"))
      (node (ref "IC1") (pin "11") (pinfunction "GND_11") (pintype "power_in"))
      (node (ref "IC1") (pin "32") (pinfunction "GND1_32") (pintype "power_in"))
      (node (ref "IC1") (pin "62") (pinfunction "GND2_62") (pintype "power_in"))
      (node (ref "IC1") (pin "81") (pinfunction "GND3_81") (pintype "power_in"))
      (node (ref "IC1") (pin "99") (pinfunction "AGND_99") (pintype "power_in"))
      (node (ref "IC3") (pin "4") (pinfunction "GND_4") (pintype "power_in"))
      (node (ref "IC4") (pin "1") (pinfunction "A0_1") (pintype "input"))
      (node (ref "IC4") (pin "2") (pinfunction "A1_2") (pintype "input"))
      (node (ref "IC4") (pin "3") (pinfunction "A2_3") (pintype "input"))
      (node (ref "IC4") (pin "4") (pinfunction "GND_4") (pintype "power_in"))
      (node (ref "IC4") (pin "7") (pinfunction "WP_7") (pintype "input"))
      (node (ref "IC5") (pin "2") (pinfunction "A1_2") (pintype "input"))
      (node (ref "IC5") (pin "3") (pinfunction "A2_3") (pintype "input"))
      (node (ref "IC5") (pin "4") (pinfunction "GND_4") (pintype "power_in"))
      (node (ref "IC5") (pin "7") (pinfunction "WP_7") (pintype "input"))
      (node (ref "M1") (pin "4") (pinfunction "S_4") (pintype "passive"))
      (node (ref "M10") (pin "10") (pinfunction "S_10") (pintype "passive"))
      (node (ref "M10") (pin "5") (pinfunction "S_5") (pintype "passive"))
      (node (ref "M11") (pin "10") (pinfunction "S_10") (pintype "passive"))
      (node (ref "M11") (pin "5") (pinfunction "S_5") (pintype "passive"))
      (node (ref "M2") (pin "4") (pinfunction "S_4") (pintype "passive"))
      (node (ref "M20") (pin "6") (pinfunction "S_6") (pintype "passive"))
      (node (ref "M21") (pin "6") (pinfunction "S_6") (pintype "passive"))
      (node (ref "M23") (pin "4") (pinfunction "S_4") (pintype "passive"))
      (node (ref "M3") (pin "4") (pinfunction "S_4") (pintype "passive"))
      (node (ref "M30") (pin "6") (pinfunction "S_6") (pintype "passive"))
      (node (ref "M31") (pin "6") (pinfunction "S_6") (pintype "passive"))
      (node (ref "M32") (pin "10") (pinfunction "S_10") (pintype "passive"))
      (node (ref "M4") (pin "4") (pinfunction "S_4") (pintype "passive"))
      (node (ref "M40") (pin "10") (pinfunction "S_10") (pintype "passive"))
      (node (ref "M41") (pin "10") (pinfunction "S_10") (pintype "passive"))
      (node (ref "M42") (pin "6") (pinfunction "S_6") (pintype "passive"))
      (node (ref "M43") (pin "6") (pinfunction "S_6") (pintype "passive"))
      (node (ref "M5") (pin "4") (pinfunction "S_4") (pintype "passive"))
      (node (ref "M50") (pin "6") (pinfunction "S_6") (pintype "passive"))
      (node (ref "M51") (pin "4") (pinfunction "S_4") (pintype "passive"))
      (node (ref "M52") (pin "8") (pinfunction "S_8") (pintype "passive"))
      (node (ref "M6") (pin "4") (pinfunction "S_4") (pintype "passive"))
      (node (ref "M7") (pin "4") (pinfunction "S_4") (pintype "passive"))
      (node (ref "M8") (pin "10") (pinfunction "S_10") (pintype "passive"))
      (node (ref "M8") (pin "5") (pinfunction "S_5") (pintype "passive"))
      (node (ref "M9") (pin "10") (pinfunction "S_10") (pintype "passive"))
      (node (ref "M9") (pin "5") (pinfunction "S_5") (pintype "passive"))
      (node (ref "R4") (pin "2") (pinfunction "2_2") (pintype "passive"))
      (node (ref "R7") (pin "2") (pinfunction "2_2") (pintype "passive"))
      (node (ref "U1") (pin "18") (pinfunction "GND2_18") (pintype "power_in"))
      (node (ref "U1") (pin "21") (pinfunction "GND3_21") (pintype "power_in"))
      (node (ref "U1") (pin "25") (pinfunction "AGND_25") (pintype "power_in"))
      (node (ref "U1") (pin "26") (pinfunction "TEST_26") (pintype "input"))
      (node (ref "U1") (pin "7") (pinfunction "GND1_7") (pintype "power_in"))
    )
    (net (code "91") (name "Net-(IC3-VBAT)") (class "Default")
      (node (ref "G1") (pin "+") (pinfunction "+_+") (pintype "passive"))
      (node (ref "IC3") (pin "3") (pinfunction "VBAT_3") (pintype "power_in"))
    )
    (net (code "92") (name "Net-(IC3-X1)") (class "Default")
      (node (ref "IC3") (pin "1") (pinfunction "X1_1") (pintype "input"))
      (node (ref "Q2") (pin "2") (pinfunction "2_2") (pintype "passive"))
    )
    (net (code "93") (name "Net-(IC3-X2)") (class "Default")
      (node (ref "IC3") (pin "2") (pinfunction "X2_2") (pintype "output"))
      (node (ref "Q2") (pin "1") (pinfunction "1_1") (pintype "passive"))
    )
    (net (code "94") (name "Net-(M21B-S)") (class "Default")
      (node (ref "M21") (pin "2") (pinfunction "S_2") (pintype "passive"))
      (node (ref "SJ1") (pin "1") (pinfunction "1_1") (pintype "passive"))
    )
    (net (code "95") (name "Net-(M23A-S)") (class "Default")
      (node (ref "M23") (pin "1") (pinfunction "S_1") (pintype "passive"))
      (node (ref "R6") (pin "1") (pinfunction "1_1") (pintype "passive"))
    )
    (net (code "96") (name "Net-(M23B-S)") (class "Default")
      (node (ref "M23") (pin "2") (pinfunction "S_2") (pintype "passive"))
      (node (ref "U1") (pin "16") (pinfunction "USBDM_16") (pintype "bidirectional"))
    )
    (net (code "97") (name "Net-(M23C-S)") (class "Default")
      (node (ref "M23") (pin "3") (pinfunction "S_3") (pintype "passive"))
      (node (ref "U1") (pin "15") (pinfunction "USBDP_15") (pintype "bidirectional"))
    )
    (net (code "98") (name "Net-(U1-3V3OUT)") (class "Default")
      (node (ref "C10") (pin "2") (pinfunction "2_2") (pintype "passive"))
      (node (ref "U1") (pin "17") (pinfunction "3V3OUT_17") (pintype "output"))
    )
    (net (code "99") (name "Net-(U1-RESET#)") (class "Default")
      (node (ref "R6") (pin "2") (pinfunction "2_2") (pintype "passive"))
      (node (ref "R7") (pin "1") (pinfunction "1_1") (pintype "passive"))
      (node (ref "U1") (pin "19") (pinfunction "RESET#_19") (pintype "input"))
    )
    (net (code "100") (name "Net-(U1-RXD)") (class "Default")
      (node (ref "R9") (pin "1") (pinfunction "1_1") (pintype "passive"))
      (node (ref "U1") (pin "5") (pinfunction "RXD_5") (pintype "input"))
    )
    (net (code "101") (name "Net-(U1-TXD)") (class "Default")
      (node (ref "R8") (pin "1") (pinfunction "1_1") (pintype "passive"))
      (node (ref "U1") (pin "1") (pinfunction "TXD_1") (pintype "output"))
    )
    (net (code "102") (name "VCC") (class "Default")
      (node (ref "C11") (pin "+") (pinfunction "+_+") (pintype "passive"))
      (node (ref "C3") (pin "2") (pinfunction "2_2") (pintype "passive"))
      (node (ref "C4") (pin "2") (pinfunction "2_2") (pintype "passive"))
      (node (ref "C6") (pin "1") (pinfunction "1_1") (pintype "passive"))
      (node (ref "C7") (pin "1") (pinfunction "1_1") (pintype "passive"))
      (node (ref "C8") (pin "1") (pinfunction "1_1") (pintype "passive"))
      (node (ref "C9") (pin "1") (pinfunction "1_1") (pintype "passive"))
      (node (ref "IC1") (pin "10") (pinfunction "VCC_10") (pintype "power_in"))
      (node (ref "IC1") (pin "31") (pinfunction "VCC1_31") (pintype "power_in"))
      (node (ref "IC1") (pin "61") (pinfunction "VCC2_61") (pintype "power_in"))
      (node (ref "IC1") (pin "80") (pinfunction "VCC3_80") (pintype "power_in"))
      (node (ref "IC3") (pin "8") (pinfunction "VCC_8") (pintype "power_in"))
      (node (ref "IC4") (pin "8") (pinfunction "VCC_8") (pintype "power_in"))
      (node (ref "IC5") (pin "1") (pinfunction "A0_1") (pintype "input"))
      (node (ref "IC5") (pin "8") (pinfunction "VCC_8") (pintype "power_in"))
      (node (ref "L1") (pin "1") (pinfunction "1_1") (pintype "passive"))
      (node (ref "M20") (pin "1") (pinfunction "S_1") (pintype "passive"))
      (node (ref "M30") (pin "1") (pinfunction "S_1") (pintype "passive"))
      (node (ref "M31") (pin "1") (pinfunction "S_1") (pintype "passive"))
      (node (ref "M32") (pin "1") (pinfunction "S_1") (pintype "passive"))
      (node (ref "M40") (pin "1") (pinfunction "S_1") (pintype "passive"))
      (node (ref "M41") (pin "1") (pinfunction "S_1") (pintype "passive"))
      (node (ref "M42") (pin "1") (pinfunction "S_1") (pintype "passive"))
      (node (ref "M43") (pin "1") (pinfunction "S_1") (pintype "passive"))
      (node (ref "M50") (pin "1") (pinfunction "S_1") (pintype "passive"))
      (node (ref "M52") (pin "1") (pinfunction "S_1") (pintype "passive"))
      (node (ref "R1") (pin "1") (pinfunction "1_1") (pintype "passive"))
      (node (ref "R2") (pin "1") (pinfunction "1_1") (pintype "passive"))
      (node (ref "R3") (pin "1") (pinfunction "1_1") (pintype "passive"))
      (node (ref "SJ1") (pin "2") (pinfunction "2_2") (pintype "passive"))
      (node (ref "U1") (pin "20") (pinfunction "VCC_20") (pintype "power_in"))
      (node (ref "U1") (pin "4") (pinfunction "VCCIO_4") (pintype "power_in"))
    )
    (net (code "103") (name "unconnected-(IC1-(OC0B)PG5-Pad1)") (class "Default")
      (node (ref "IC1") (pin "1") (pinfunction "(OC0B)PG5_1") (pintype "bidirectional"))
    )
    (net (code "104") (name "unconnected-(IC1-PH6(OC2B)-Pad18)") (class "Default")
      (node (ref "IC1") (pin "18") (pinfunction "PH6(OC2B)_18") (pintype "bidirectional"))
    )
    (net (code "105") (name "unconnected-(IC1-PH7(T4)-Pad27)") (class "Default")
      (node (ref "IC1") (pin "27") (pinfunction "PH7(T4)_27") (pintype "bidirectional"))
    )
    (net (code "106") (name "unconnected-(IC3-SQW{slash}OUT-Pad7)") (class "Default")
      (node (ref "IC3") (pin "7") (pinfunction "SQW/OUT_7") (pintype "output"))
    )
    (net (code "107") (name "unconnected-(U1-CBUS0-Pad23)") (class "Default")
      (node (ref "U1") (pin "23") (pinfunction "CBUS0_23") (pintype "bidirectional"))
    )
    (net (code "108") (name "unconnected-(U1-CBUS1-Pad22)") (class "Default")
      (node (ref "U1") (pin "22") (pinfunction "CBUS1_22") (pintype "bidirectional"))
    )
    (net (code "109") (name "unconnected-(U1-CBUS2-Pad13)") (class "Default")
      (node (ref "U1") (pin "13") (pinfunction "CBUS2_13") (pintype "bidirectional"))
    )
    (net (code "110") (name "unconnected-(U1-CBUS3-Pad14)") (class "Default")
      (node (ref "U1") (pin "14") (pinfunction "CBUS3_14") (pintype "bidirectional"))
    )
    (net (code "111") (name "unconnected-(U1-CBUS4-Pad12)") (class "Default")
      (node (ref "U1") (pin "12") (pinfunction "CBUS4_12") (pintype "bidirectional"))
    )
    (net (code "112") (name "unconnected-(U1-CTS#-Pad11)") (class "Default")
      (node (ref "U1") (pin "11") (pinfunction "CTS#_11") (pintype "input"))
    )
    (net (code "113") (name "unconnected-(U1-DCD#-Pad10)") (class "Default")
      (node (ref "U1") (pin "10") (pinfunction "DCD#_10") (pintype "input"))
    )
    (net (code "114") (name "unconnected-(U1-DSR#-Pad9)") (class "Default")
      (node (ref "U1") (pin "9") (pinfunction "DSR#_9") (pintype "input"))
    )
    (net (code "115") (name "unconnected-(U1-DTR#-Pad2)") (class "Default")
      (node (ref "U1") (pin "2") (pinfunction "DTR#_2") (pintype "output"))
    )
    (net (code "116") (name "unconnected-(U1-OSCI-Pad27)") (class "Default")
      (node (ref "U1") (pin "27") (pinfunction "OSCI_27") (pintype "input"))
    )
    (net (code "117") (name "unconnected-(U1-OSCO-Pad28)") (class "Default")
      (node (ref "U1") (pin "28") (pinfunction "OSCO_28") (pintype "output"))
    )
    (net (code "118") (name "unconnected-(U1-RI#-Pad6)") (class "Default")
      (node (ref "U1") (pin "6") (pinfunction "RI#_6") (pintype "input"))
    )
    (net (code "119") (name "unconnected-(U1-RTS#-Pad3)") (class "Default")
      (node (ref "U1") (pin "3") (pinfunction "RTS#_3") (pintype "output"))
    )
  )
)
